# low_current_buck_reg.net
KiCad netlist of a schematic drawn in Altium Designer
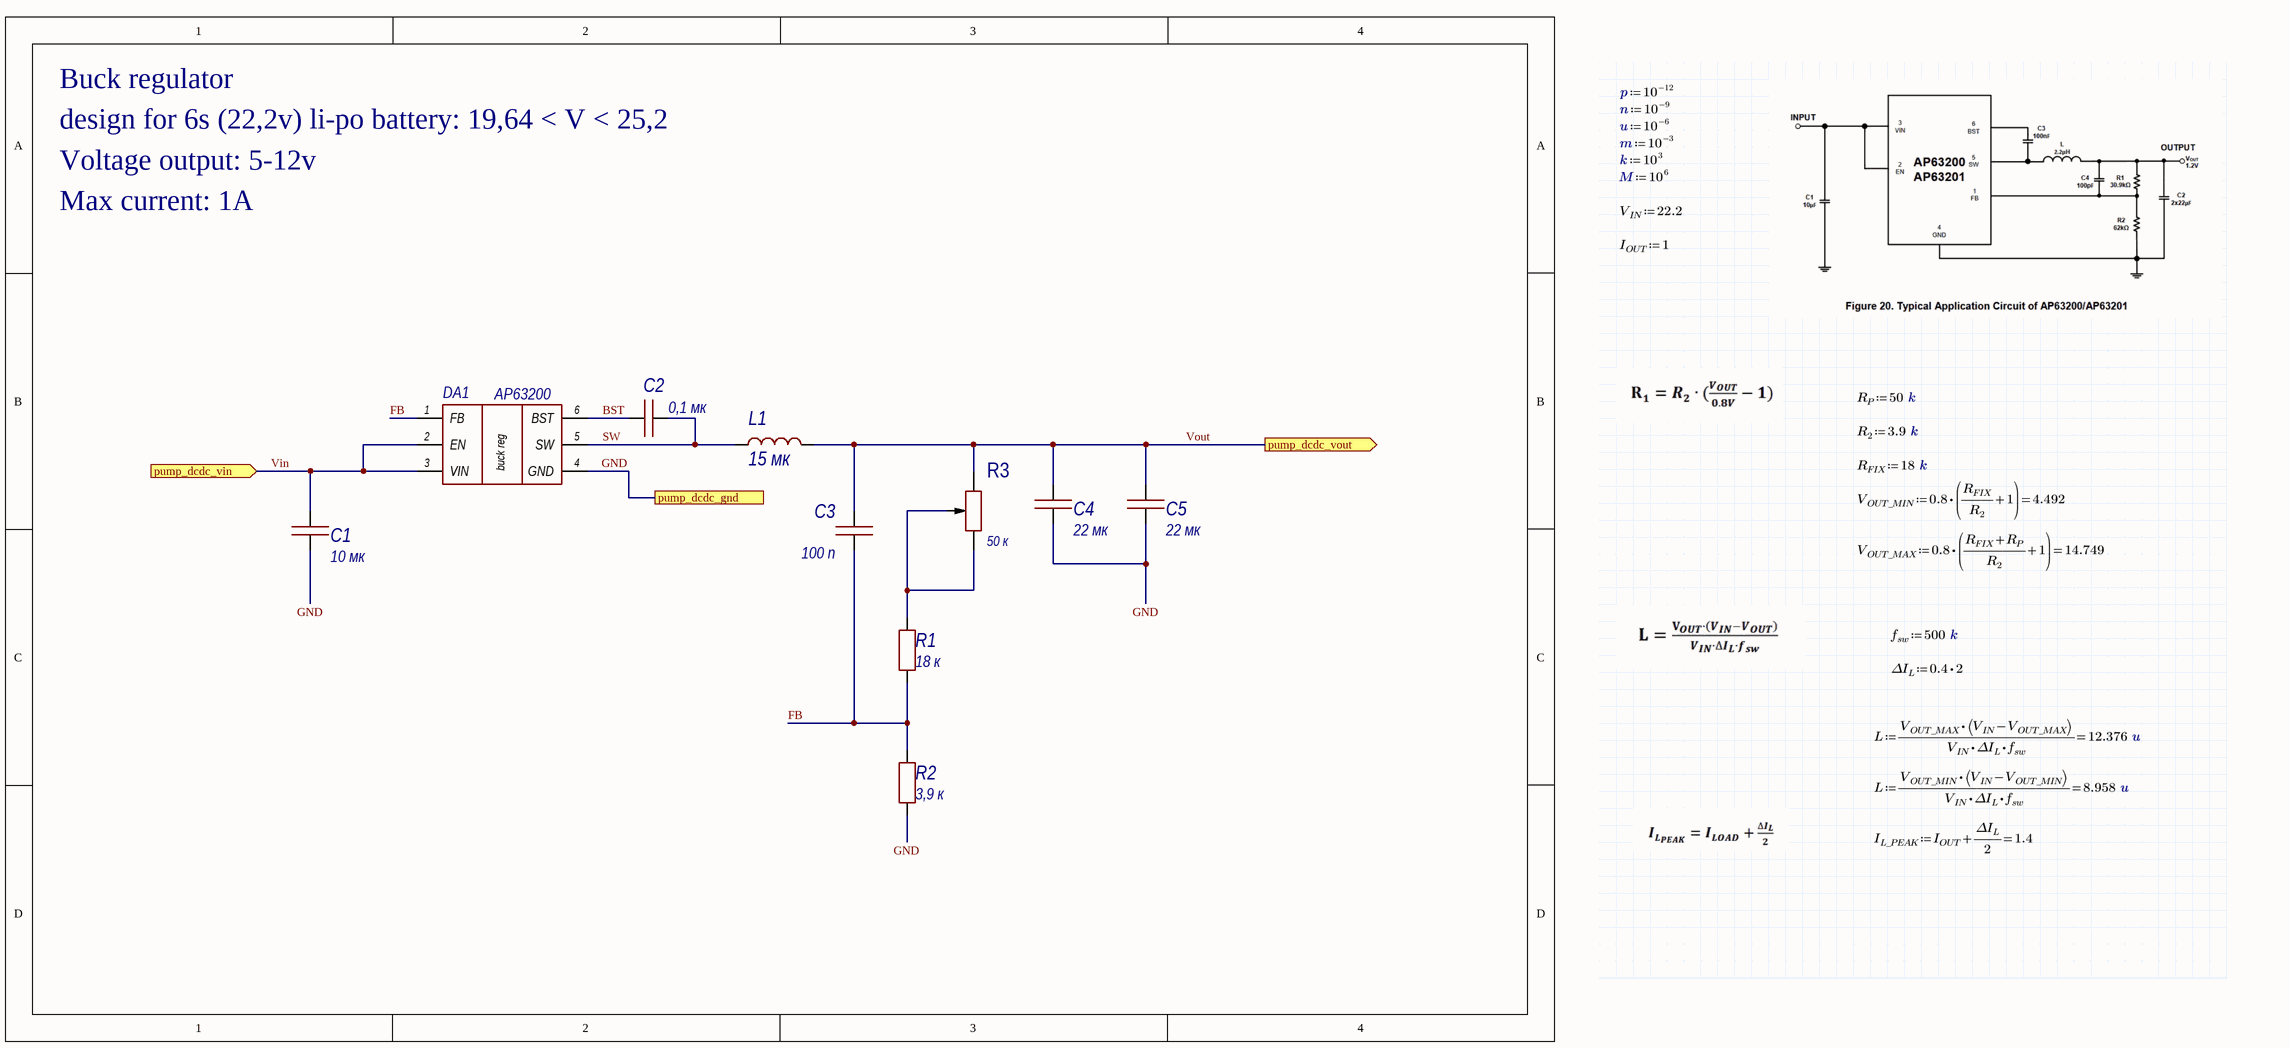
[diagram p0: low_current_buck_reg.SchDoc]

(export (version "E")
  (design (tool "Eeschema 10.0.6"))
  (components
    (comp (ref "C1")
      (value "10 мк")
      (footprint "1210C")
      (description "Конденсатор")
      (fields (field (name "PART NUMBER") "Capacitor_10u_10_35V_X7R_1210C") (field (name "TOLERANCE") "0,1"))
      (libsource (lib "Hydrolib") (part "Capacitor"))
    )
    (comp (ref "C2")
      (value "0,1 мк")
      (footprint "0603C")
      (description "Конденсатор")
      (fields (field (name "PART NUMBER") "Capacitor_0,1u_10_50V_X7R_0603C") (field (name "TOLERANCE") "0,1"))
      (libsource (lib "Hydrolib") (part "Capacitor"))
    )
    (comp (ref "C3")
      (value "100 п")
      (footprint "0603C")
      (description "Конденсатор")
      (fields (field (name "PART NUMBER") "Capacitor_100p_10_50V_X7R_0603C") (field (name "TOLERANCE") "0,1"))
      (libsource (lib "Hydrolib") (part "Capacitor"))
    )
    (comp (ref "C4")
      (value "22 мк")
      (footprint "1210C")
      (description "Конденсатор")
      (fields (field (name "PART NUMBER") "Capacitor_22u_10_25V_X7R_1210C") (field (name "TOLERANCE") "0,1"))
      (libsource (lib "Hydrolib") (part "Capacitor"))
    )
    (comp (ref "C5")
      (value "22 мк")
      (footprint "1210C")
      (description "Конденсатор")
      (fields (field (name "PART NUMBER") "Capacitor_22u_10_25V_X7R_1210C") (field (name "TOLERANCE") "0,1"))
      (libsource (lib "Hydrolib") (part "Capacitor"))
    )
    (comp (ref "DA1")
      (value "AP63200")
      (footprint "TSOT26")
      (description "DC-DC понижающий преобразователь, Vin: 3.8 - 40 В, adj, 2 А")
      (libsource (lib "Hydrolib") (part "AP63200"))
    )
    (comp (ref "L1")
      (value "15 мк")
      (footprint "SP43")
      (description "Индуктивность на 15 мкГн, номинальный ток 1,3 А")
      (fields (field (name "PART NUMBER") "SP43-150K"))
      (libsource (lib "Hydrolib") (part "Inductance"))
    )
    (comp (ref "R1")
      (value "18 к")
      (footprint "0603R")
      (description "Резистор номиналом 18 кОм и точностью 1%")
      (fields (field (name "PART NUMBER") "Resistor_18k_1_0603") (field (name "TOLERANCE") "1%"))
      (libsource (lib "Hydrolib") (part "Resistor"))
    )
    (comp (ref "R2")
      (value "3,9 к")
      (footprint "0603R")
      (description "Резистор номиналом 3,9 кОм и точностью 1%")
      (fields (field (name "PART NUMBER") "Resistor_3.9k_1_0603") (field (name "TOLERANCE") "1%"))
      (libsource (lib "Hydrolib") (part "Resistor"))
    )
    (comp (ref "R3")
      (value "50 к")
      (footprint "3mm_trim")
      (description "Потенциометр однооборотный керметный 50кОм 0.1Вт ±25% SMD лента на катушке")
      (fields (field (name "PART NUMBER") "TC33X-2-503E") (field (name "TOLERANCE") "50%"))
      (libsource (lib "Hydrolib") (part "trim_res"))
    )
  )
  (nets
    (net (code "1") (name "/BST") (class "Default")
      (node (ref "C2") (pin "1") (pinfunction "1_1") (pintype "passive"))
      (node (ref "DA1") (pin "6") (pinfunction "BST_6") (pintype "passive"))
    )
    (net (code "2") (name "/FB") (class "Default")
      (node (ref "C3") (pin "1") (pinfunction "1_1") (pintype "passive"))
      (node (ref "DA1") (pin "1") (pinfunction "FB_1") (pintype "passive"))
      (node (ref "R1") (pin "1") (pinfunction "1_1") (pintype "passive"))
      (node (ref "R2") (pin "2") (pinfunction "2_2") (pintype "passive"))
    )
    (net (code "3") (name "/GND") (class "Default")
      (node (ref "C1") (pin "1") (pinfunction "1_1") (pintype "passive"))
      (node (ref "C4") (pin "1") (pinfunction "1_1") (pintype "passive"))
      (node (ref "C5") (pin "1") (pinfunction "1_1") (pintype "passive"))
      (node (ref "DA1") (pin "4") (pinfunction "GND_4") (pintype "passive"))
      (node (ref "R2") (pin "1") (pinfunction "1_1") (pintype "passive"))
    )
    (net (code "4") (name "/SW") (class "Default")
      (node (ref "C2") (pin "2") (pinfunction "2_2") (pintype "passive"))
      (node (ref "DA1") (pin "5") (pinfunction "SW_5") (pintype "passive"))
      (node (ref "L1") (pin "1") (pinfunction "1_1") (pintype "passive"))
    )
    (net (code "5") (name "/Vin") (class "Default")
      (node (ref "C1") (pin "2") (pinfunction "2_2") (pintype "passive"))
      (node (ref "DA1") (pin "2") (pinfunction "EN_2") (pintype "passive"))
      (node (ref "DA1") (pin "3") (pinfunction "VIN_3") (pintype "passive"))
    )
    (net (code "6") (name "/Vout") (class "Default")
      (node (ref "C3") (pin "2") (pinfunction "2_2") (pintype "passive"))
      (node (ref "C4") (pin "2") (pinfunction "2_2") (pintype "passive"))
      (node (ref "C5") (pin "2") (pinfunction "2_2") (pintype "passive"))
      (node (ref "L1") (pin "2") (pinfunction "2_2") (pintype "passive"))
      (node (ref "R3") (pin "3") (pinfunction "3_3") (pintype "passive"))
    )
    (net (code "7") (name "Net-(R1-Pad2)") (class "Default")
      (node (ref "R1") (pin "2") (pinfunction "2_2") (pintype "passive"))
      (node (ref "R3") (pin "1") (pinfunction "1_1") (pintype "passive"))
      (node (ref "R3") (pin "2") (pinfunction "2_2") (pintype "passive"))
    )
  )
)
